# GL3520_4_Ports.net
KiCad netlist of a schematic drawn in Altium Designer
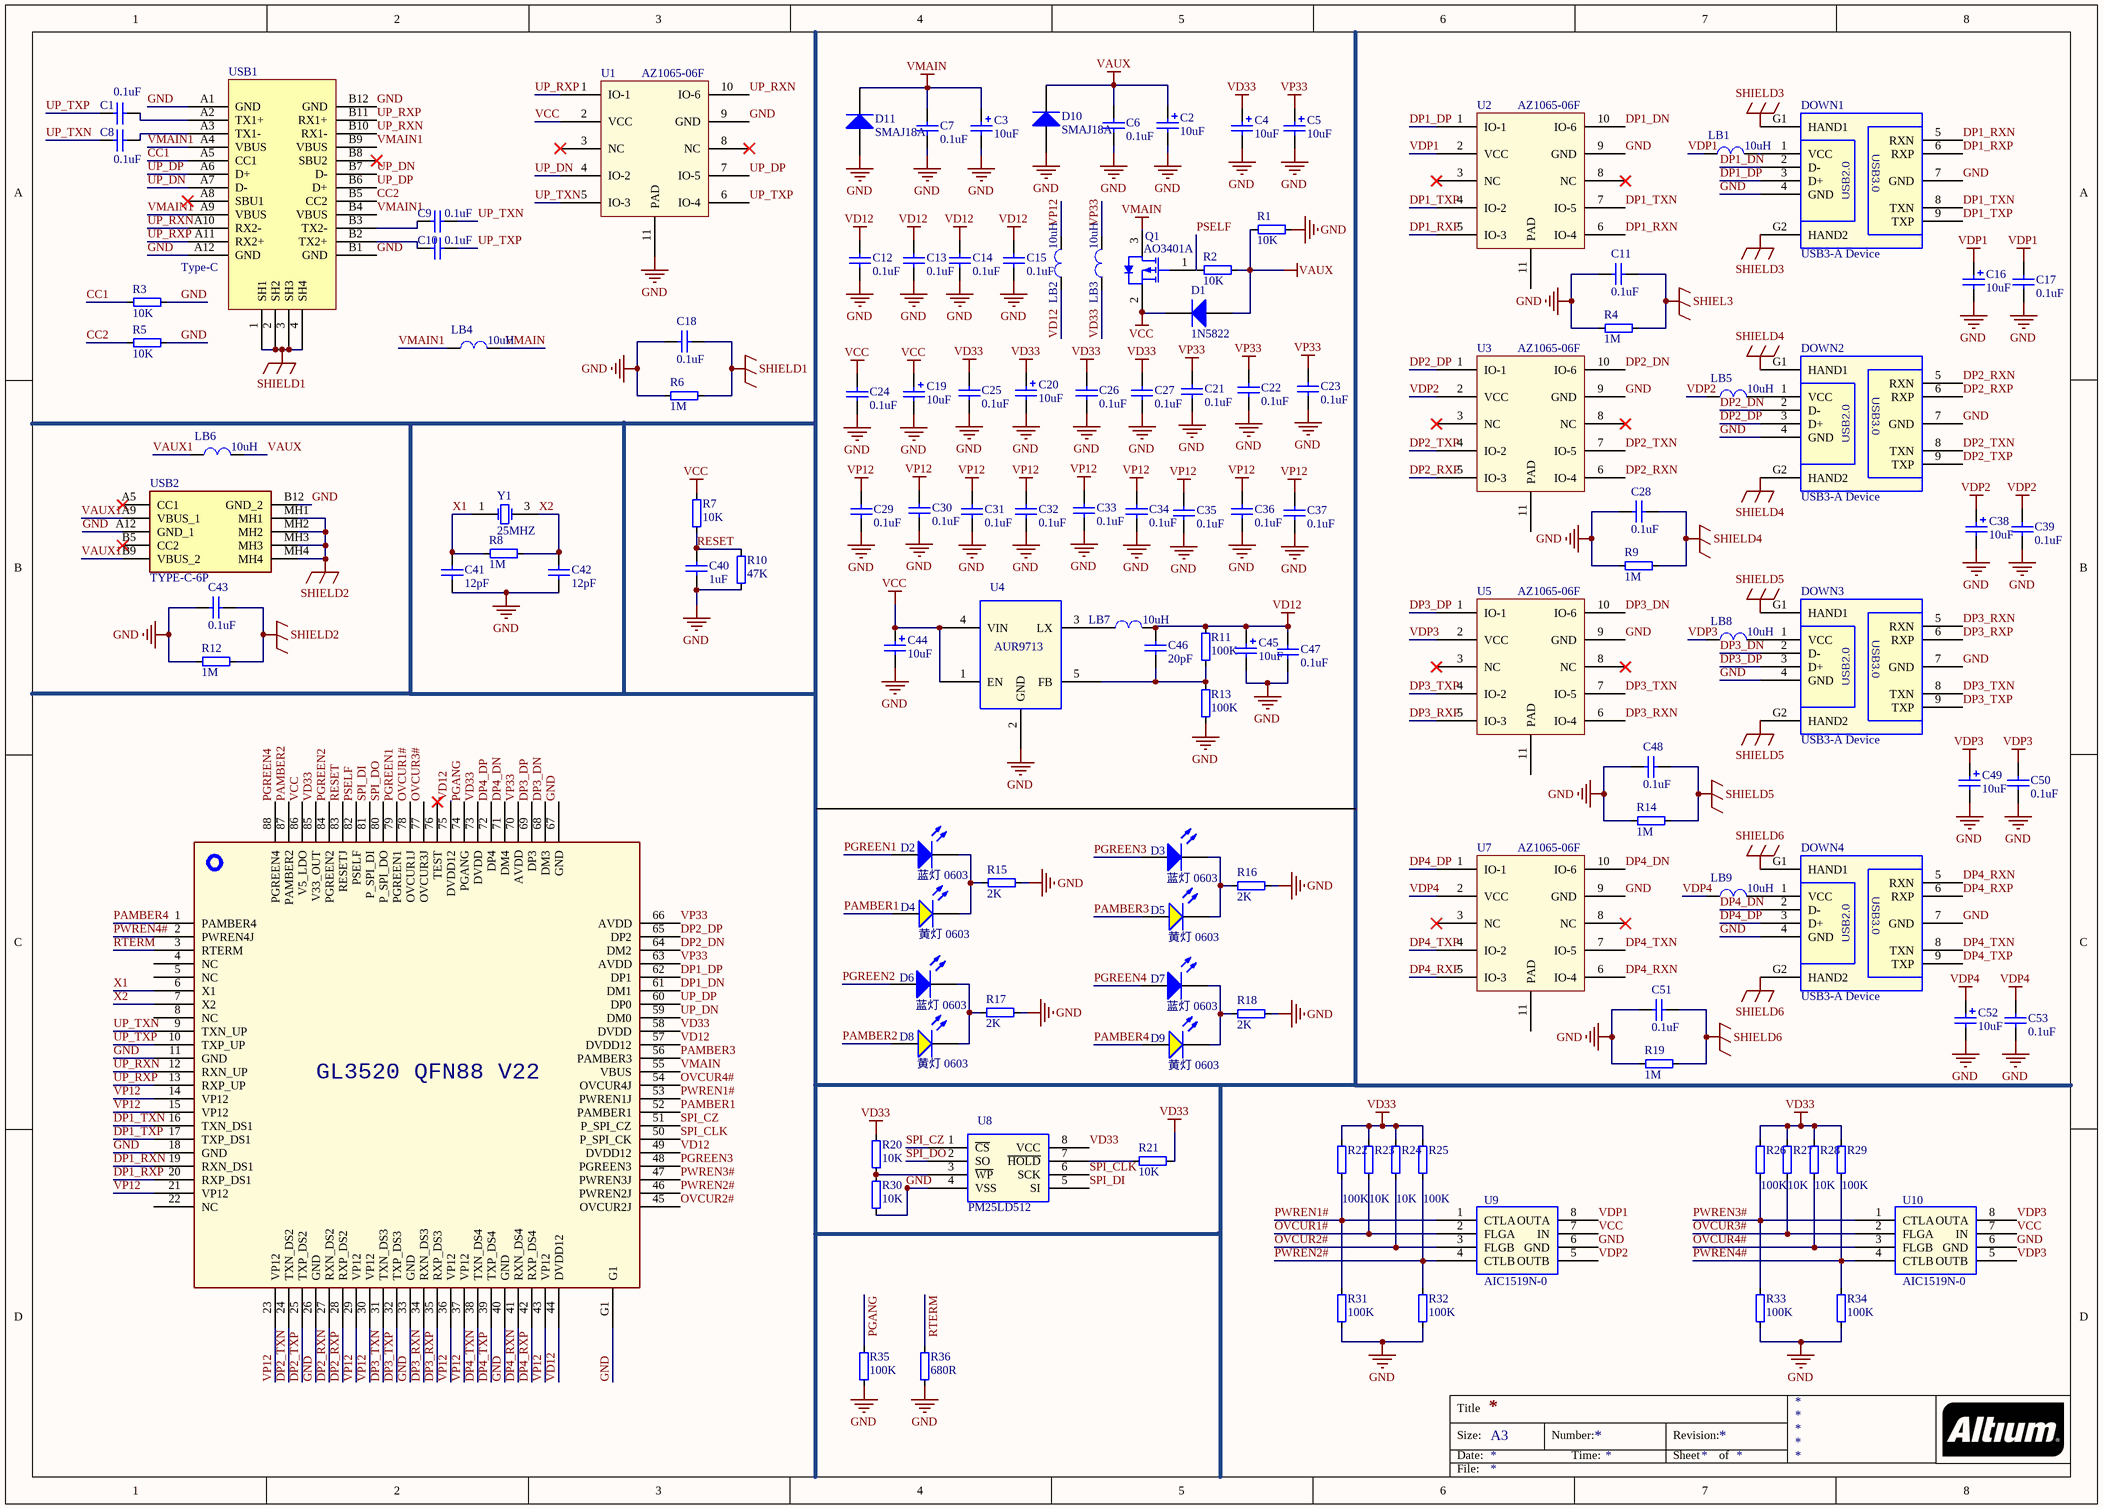
[diagram p0: GL3520 4 Ports.SchDoc]

(export (version "E")
  (design (tool "Eeschema 10.0.6"))
  (components
    (comp (ref "C1")
      (value "0.1uF")
      (footprint "C 0603_L")
      (description "贴片电容")
      (libsource (lib "嘉立创") (part "0603 2.2uF (225) 10% 16V"))
    )
    (comp (ref "C2")
      (value "10uF")
      (footprint "CASE-A_3216")
      (description "钽电容1206")
      (libsource (lib "嘉立创") (part "3216 10uF (106) 10% 16V"))
    )
    (comp (ref "C3")
      (value "10uF")
      (footprint "CASE-A_3216")
      (description "钽电容1206")
      (libsource (lib "嘉立创") (part "3216 10uF (106) 10% 16V"))
    )
    (comp (ref "C4")
      (value "10uF")
      (footprint "CASE-A_3216")
      (description "钽电容")
      (libsource (lib "嘉立创") (part "3216 10uF (106) 10% 16V"))
    )
    (comp (ref "C5")
      (value "10uF")
      (footprint "CASE-A_3216")
      (description "钽电容")
      (libsource (lib "嘉立创") (part "3216 10uF (106) 10% 16V"))
    )
    (comp (ref "C6")
      (value "0.1uF")
      (footprint "C 0603_L")
      (description "贴片电容")
      (libsource (lib "嘉立创") (part "0603 2.2uF (225) 10% 16V"))
    )
    (comp (ref "C7")
      (value "0.1uF")
      (footprint "C 0603_L")
      (description "贴片电容")
      (libsource (lib "嘉立创") (part "0603 2.2uF (225) 10% 16V"))
    )
    (comp (ref "C8")
      (value "0.1uF")
      (footprint "C 0603_L")
      (description "贴片电容")
      (libsource (lib "嘉立创") (part "0603 2.2uF (225) 10% 16V"))
    )
    (comp (ref "C9")
      (value "0.1uF")
      (footprint "C 0603_L")
      (description "贴片电容")
      (libsource (lib "嘉立创") (part "0603 2.2uF (225) 10% 16V"))
    )
    (comp (ref "C10")
      (value "0.1uF")
      (footprint "C 0603_L")
      (description "贴片电容")
      (libsource (lib "嘉立创") (part "0603 2.2uF (225) 10% 16V"))
    )
    (comp (ref "C11")
      (value "0.1uF")
      (footprint "C 0603_L")
      (description "贴片电容")
      (libsource (lib "嘉立创") (part "0603 2.2uF (225) 10% 16V"))
    )
    (comp (ref "C12")
      (value "0.1uF")
      (footprint "C 0603_L")
      (description "贴片电容")
      (libsource (lib "嘉立创") (part "0603 2.2uF (225) 10% 16V"))
    )
    (comp (ref "C13")
      (value "0.1uF")
      (footprint "C 0603_L")
      (description "贴片电容")
      (libsource (lib "嘉立创") (part "0603 2.2uF (225) 10% 16V"))
    )
    (comp (ref "C14")
      (value "0.1uF")
      (footprint "C 0603_L")
      (description "贴片电容")
      (libsource (lib "嘉立创") (part "0603 2.2uF (225) 10% 16V"))
    )
    (comp (ref "C15")
      (value "0.1uF")
      (footprint "C 0603_L")
      (description "贴片电容")
      (libsource (lib "嘉立创") (part "0603 2.2uF (225) 10% 16V"))
    )
    (comp (ref "C16")
      (value "10uF")
      (footprint "CASE-A_3216")
      (description "钽电容")
      (libsource (lib "嘉立创") (part "3216 10uF (106) 10% 16V"))
    )
    (comp (ref "C17")
      (value "0.1uF")
      (footprint "C 0603_L")
      (description "贴片电容")
      (libsource (lib "嘉立创") (part "0603 2.2uF (225) 10% 16V"))
    )
    (comp (ref "C18")
      (value "0.1uF")
      (footprint "C 0603_L")
      (description "贴片电容")
      (libsource (lib "嘉立创") (part "0603 2.2uF (225) 10% 16V"))
    )
    (comp (ref "C19")
      (value "10uF")
      (footprint "CASE-A_3216")
      (description "钽电容1206")
      (libsource (lib "嘉立创") (part "3216 10uF (106) 10% 16V"))
    )
    (comp (ref "C20")
      (value "10uF")
      (footprint "CASE-A_3216")
      (description "钽电容1206")
      (libsource (lib "嘉立创") (part "3216 10uF (106) 10% 16V"))
    )
    (comp (ref "C21")
      (value "0.1uF")
      (footprint "C 0603_L")
      (description "贴片电容")
      (libsource (lib "嘉立创") (part "0603 2.2uF (225) 10% 16V"))
    )
    (comp (ref "C22")
      (value "0.1uF")
      (footprint "C 0603_L")
      (description "贴片电容")
      (libsource (lib "嘉立创") (part "0603 2.2uF (225) 10% 16V"))
    )
    (comp (ref "C23")
      (value "0.1uF")
      (footprint "C 0603_L")
      (description "贴片电容")
      (libsource (lib "嘉立创") (part "0603 2.2uF (225) 10% 16V"))
    )
    (comp (ref "C24")
      (value "0.1uF")
      (footprint "C 0603_L")
      (description "贴片电容")
      (libsource (lib "嘉立创") (part "0603 2.2uF (225) 10% 16V"))
    )
    (comp (ref "C25")
      (value "0.1uF")
      (footprint "C 0603_L")
      (description "贴片电容")
      (libsource (lib "嘉立创") (part "0603 2.2uF (225) 10% 16V"))
    )
    (comp (ref "C26")
      (value "0.1uF")
      (footprint "C 0603_L")
      (description "贴片电容")
      (libsource (lib "嘉立创") (part "0603 2.2uF (225) 10% 16V"))
    )
    (comp (ref "C27")
      (value "0.1uF")
      (footprint "C 0603_L")
      (description "贴片电容")
      (libsource (lib "嘉立创") (part "0603 2.2uF (225) 10% 16V"))
    )
    (comp (ref "C28")
      (value "0.1uF")
      (footprint "C 0603_L")
      (description "贴片电容")
      (libsource (lib "嘉立创") (part "0603 2.2uF (225) 10% 16V"))
    )
    (comp (ref "C29")
      (value "0.1uF")
      (footprint "C 0603_L")
      (description "贴片电容")
      (libsource (lib "嘉立创") (part "0603 2.2uF (225) 10% 16V"))
    )
    (comp (ref "C30")
      (value "0.1uF")
      (footprint "C 0603_L")
      (description "贴片电容")
      (libsource (lib "嘉立创") (part "0603 2.2uF (225) 10% 16V"))
    )
    (comp (ref "C31")
      (value "0.1uF")
      (footprint "C 0603_L")
      (description "贴片电容")
      (libsource (lib "嘉立创") (part "0603 2.2uF (225) 10% 16V"))
    )
    (comp (ref "C32")
      (value "0.1uF")
      (footprint "C 0603_L")
      (description "贴片电容")
      (libsource (lib "嘉立创") (part "0603 2.2uF (225) 10% 16V"))
    )
    (comp (ref "C33")
      (value "0.1uF")
      (footprint "C 0603_L")
      (description "贴片电容")
      (libsource (lib "嘉立创") (part "0603 2.2uF (225) 10% 16V"))
    )
    (comp (ref "C34")
      (value "0.1uF")
      (footprint "C 0603_L")
      (description "贴片电容")
      (libsource (lib "嘉立创") (part "0603 2.2uF (225) 10% 16V"))
    )
    (comp (ref "C35")
      (value "0.1uF")
      (footprint "C 0603_L")
      (description "贴片电容")
      (libsource (lib "嘉立创") (part "0603 2.2uF (225) 10% 16V"))
    )
    (comp (ref "C36")
      (value "0.1uF")
      (footprint "C 0603_L")
      (description "贴片电容")
      (libsource (lib "嘉立创") (part "0603 2.2uF (225) 10% 16V"))
    )
    (comp (ref "C37")
      (value "0.1uF")
      (footprint "C 0603_L")
      (description "贴片电容")
      (libsource (lib "嘉立创") (part "0603 2.2uF (225) 10% 16V"))
    )
    (comp (ref "C38")
      (value "10uF")
      (footprint "CASE-A_3216")
      (description "钽电容")
      (libsource (lib "嘉立创") (part "3216 10uF (106) 10% 16V"))
    )
    (comp (ref "C39")
      (value "0.1uF")
      (footprint "C 0603_L")
      (description "贴片电容")
      (libsource (lib "嘉立创") (part "0603 2.2uF (225) 10% 16V"))
    )
    (comp (ref "C40")
      (value "1uF")
      (footprint "C 0603_L")
      (description "贴片电容")
      (libsource (lib "嘉立创") (part "0603 2.2uF (225) 10% 16V"))
    )
    (comp (ref "C41")
      (value "12pF")
      (footprint "C 0603_L")
      (description "贴片电容")
      (libsource (lib "嘉立创") (part "0603 2.2uF (225) 10% 16V"))
    )
    (comp (ref "C42")
      (value "12pF")
      (footprint "C 0603_L")
      (description "贴片电容")
      (libsource (lib "嘉立创") (part "0603 2.2uF (225) 10% 16V"))
    )
    (comp (ref "C43")
      (value "0.1uF")
      (footprint "C 0603_L")
      (description "贴片电容")
      (libsource (lib "嘉立创") (part "0603 2.2uF (225) 10% 16V"))
    )
    (comp (ref "C44")
      (value "10uF")
      (footprint "CASE-A_3216")
      (description "钽电容")
      (libsource (lib "嘉立创") (part "3216 10uF (106) 10% 16V"))
    )
    (comp (ref "C45")
      (value "10uF")
      (footprint "CASE-A_3216")
      (description "钽电容")
      (libsource (lib "嘉立创") (part "3216 10uF (106) 10% 16V"))
    )
    (comp (ref "C46")
      (value "20pF")
      (footprint "C 0603_L")
      (description "贴片电容")
      (libsource (lib "嘉立创") (part "0603 2.2uF (225) 10% 16V"))
    )
    (comp (ref "C47")
      (value "0.1uF")
      (footprint "C 0603_L")
      (description "贴片电容")
      (libsource (lib "嘉立创") (part "0603 2.2uF (225) 10% 16V"))
    )
    (comp (ref "C48")
      (value "0.1uF")
      (footprint "C 0603_L")
      (description "贴片电容")
      (libsource (lib "嘉立创") (part "0603 2.2uF (225) 10% 16V"))
    )
    (comp (ref "C49")
      (value "10uF")
      (footprint "CASE-A_3216")
      (description "钽电容")
      (libsource (lib "嘉立创") (part "3216 10uF (106) 10% 16V"))
    )
    (comp (ref "C50")
      (value "0.1uF")
      (footprint "C 0603_L")
      (description "贴片电容")
      (libsource (lib "嘉立创") (part "0603 2.2uF (225) 10% 16V"))
    )
    (comp (ref "C51")
      (value "0.1uF")
      (footprint "C 0603_L")
      (description "贴片电容")
      (libsource (lib "嘉立创") (part "0603 2.2uF (225) 10% 16V"))
    )
    (comp (ref "C52")
      (value "10uF")
      (footprint "CASE-A_3216")
      (description "钽电容")
      (libsource (lib "嘉立创") (part "3216 10uF (106) 10% 16V"))
    )
    (comp (ref "C53")
      (value "0.1uF")
      (footprint "C 0603_L")
      (description "贴片电容")
      (libsource (lib "嘉立创") (part "0603 2.2uF (225) 10% 16V"))
    )
    (comp (ref "D1")
      (value "1N5822")
      (footprint "SMA")
      (description "3 Amp General Purpose Rectifier")
      (fields (field (name "PUBLISHER") "Altium Limited"))
      (libsource (lib "Miscellaneous Devices") (part "Diode 1N5400"))
    )
    (comp (ref "D2")
      (value "蓝灯 0603")
      (footprint "0603_LED_S1")
      (description "发光二极管")
      (libsource (lib "嘉立创") (part "0603 蓝灯"))
    )
    (comp (ref "D3")
      (value "蓝灯 0603")
      (footprint "0603_LED_S1")
      (description "发光二极管")
      (libsource (lib "嘉立创") (part "0603 蓝灯"))
    )
    (comp (ref "D4")
      (value "黄灯 0603")
      (footprint "0603_LED_S1")
      (description "发光二极管")
      (libsource (lib "嘉立创") (part "0603 黄灯"))
    )
    (comp (ref "D5")
      (value "黄灯 0603")
      (footprint "0603_LED_S1")
      (description "发光二极管")
      (libsource (lib "嘉立创") (part "0603 黄灯"))
    )
    (comp (ref "D6")
      (value "蓝灯 0603")
      (footprint "0603_LED_S1")
      (description "发光二极管")
      (libsource (lib "嘉立创") (part "0603 蓝灯"))
    )
    (comp (ref "D7")
      (value "蓝灯 0603")
      (footprint "0603_LED_S1")
      (description "发光二极管")
      (libsource (lib "嘉立创") (part "0603 蓝灯"))
    )
    (comp (ref "D8")
      (value "黄灯 0603")
      (footprint "0603_LED_S1")
      (description "发光二极管")
      (libsource (lib "嘉立创") (part "0603 黄灯"))
    )
    (comp (ref "D9")
      (value "黄灯 0603")
      (footprint "0603_LED_S1")
      (description "发光二极管")
      (libsource (lib "嘉立创") (part "0603 黄灯"))
    )
    (comp (ref "D10")
      (value "SMAJ18A")
      (footprint "DIO-214AC")
      (description "3 Amp General Purpose Rectifier")
      (fields (field (name "PUBLISHER") "Altium Limited"))
      (libsource (lib "Miscellaneous Devices") (part "Diode 1N5400"))
    )
    (comp (ref "D11")
      (value "SMAJ18A")
      (footprint "DIO-214AC")
      (description "3 Amp General Purpose Rectifier")
      (fields (field (name "PUBLISHER") "Altium Limited"))
      (libsource (lib "Miscellaneous Devices") (part "Diode 1N5400"))
    )
    (comp (ref "DOWN1")
      (value "USB3-A Device")
      (footprint "USB3.0-2 - duplicate")
      (libsource (lib "*") (part "USB3-A_5"))
    )
    (comp (ref "DOWN2")
      (value "USB3-A Device")
      (footprint "USB3.0-2 - duplicate")
      (libsource (lib "*") (part "USB3-A_5"))
    )
    (comp (ref "DOWN3")
      (value "USB3-A Device")
      (footprint "USB3.0-2 - duplicate")
      (libsource (lib "*") (part "USB3-A_5"))
    )
    (comp (ref "DOWN4")
      (value "USB3-A Device")
      (footprint "USB3.0-2 - duplicate")
      (libsource (lib "*") (part "USB3-A_5"))
    )
    (comp (ref "LB1") (value "10uH") (footprint "CDRH74") (libsource (lib "*") (part "L-0603")))
    (comp (ref "LB2") (value "10uH") (footprint "CDRH74") (libsource (lib "*") (part "L-0603")))
    (comp (ref "LB3") (value "10uH") (footprint "CDRH74") (libsource (lib "*") (part "L-0603")))
    (comp (ref "LB4") (value "10uH") (footprint "CDRH74") (libsource (lib "*") (part "L-0603")))
    (comp (ref "LB5") (value "10uH") (footprint "CDRH74") (libsource (lib "*") (part "L-0603")))
    (comp (ref "LB6") (value "10uH") (footprint "CDRH74") (libsource (lib "*") (part "L-0603")))
    (comp (ref "LB7") (value "10uH") (footprint "CDRH74") (libsource (lib "*") (part "L-0603")))
    (comp (ref "LB8") (value "10uH") (footprint "CDRH74") (libsource (lib "*") (part "L-0603")))
    (comp (ref "LB9") (value "10uH") (footprint "CDRH74") (libsource (lib "*") (part "L-0603")))
    (comp (ref "Q1")
      (value "AO3401A")
      (footprint "SOT23-3L")
      (description "P-Channel MOSFET, 30 V, 4 A, -55 to 150 degC, 3-Pin SOT-23-3L, RoHS, Tape and Reel")
      (fields (field (name "MANUFACTURER") "Alpha and Omega"))
      (libsource (lib "GL3520 4 Ports") (part "CMP-2000-05778-1"))
    )
    (comp (ref "R1") (value "10K") (footprint "R 0603_L") (libsource (lib "Jlink OB") (part "RES")))
    (comp (ref "R2") (value "10K") (footprint "R 0603_L") (libsource (lib "Jlink OB") (part "RES")))
    (comp (ref "R3") (value "10K") (footprint "R 0603_L") (libsource (lib "Jlink OB") (part "RES")))
    (comp (ref "R4") (value "1M") (footprint "R 0603_L") (libsource (lib "Jlink OB") (part "RES")))
    (comp (ref "R5") (value "10K") (footprint "R 0603_L") (libsource (lib "Jlink OB") (part "RES")))
    (comp (ref "R6") (value "1M") (footprint "R 0603_L") (libsource (lib "Jlink OB") (part "RES")))
    (comp (ref "R7") (value "10K") (footprint "R 0603_L") (libsource (lib "Jlink OB") (part "RES")))
    (comp (ref "R8") (value "1M") (footprint "R 0603_L") (libsource (lib "Jlink OB") (part "RES")))
    (comp (ref "R9") (value "1M") (footprint "R 0603_L") (libsource (lib "Jlink OB") (part "RES")))
    (comp (ref "R10") (value "47K") (footprint "R 0603_L") (libsource (lib "Jlink OB") (part "RES")))
    (comp (ref "R11") (value "100K") (footprint "R 0603_L") (libsource (lib "Jlink OB") (part "RES")))
    (comp (ref "R12") (value "1M") (footprint "R 0603_L") (libsource (lib "Jlink OB") (part "RES")))
    (comp (ref "R13") (value "100K") (footprint "R 0603_L") (libsource (lib "Jlink OB") (part "RES")))
    (comp (ref "R14") (value "1M") (footprint "R 0603_L") (libsource (lib "Jlink OB") (part "RES")))
    (comp (ref "R15") (value "2K") (footprint "R 0603_L") (libsource (lib "Jlink OB") (part "RES")))
    (comp (ref "R16") (value "2K") (footprint "R 0603_L") (libsource (lib "Jlink OB") (part "RES")))
    (comp (ref "R17") (value "2K") (footprint "R 0603_L") (libsource (lib "Jlink OB") (part "RES")))
    (comp (ref "R18") (value "2K") (footprint "R 0603_L") (libsource (lib "Jlink OB") (part "RES")))
    (comp (ref "R19") (value "1M") (footprint "R 0603_L") (libsource (lib "Jlink OB") (part "RES")))
    (comp (ref "R20") (value "10K") (footprint "R 0603_L") (libsource (lib "Jlink OB") (part "RES")))
    (comp (ref "R21") (value "10K") (footprint "R 0603_L") (libsource (lib "Jlink OB") (part "RES")))
    (comp (ref "R22") (value "100K") (footprint "R 0603_L") (libsource (lib "Jlink OB") (part "RES")))
    (comp (ref "R23") (value "10K") (footprint "R 0603_L") (libsource (lib "Jlink OB") (part "RES")))
    (comp (ref "R24") (value "10K") (footprint "R 0603_L") (libsource (lib "Jlink OB") (part "RES")))
    (comp (ref "R25") (value "100K") (footprint "R 0603_L") (libsource (lib "Jlink OB") (part "RES")))
    (comp (ref "R26") (value "100K") (footprint "R 0603_L") (libsource (lib "Jlink OB") (part "RES")))
    (comp (ref "R27") (value "10K") (footprint "R 0603_L") (libsource (lib "Jlink OB") (part "RES")))
    (comp (ref "R28") (value "10K") (footprint "R 0603_L") (libsource (lib "Jlink OB") (part "RES")))
    (comp (ref "R29") (value "100K") (footprint "R 0603_L") (libsource (lib "Jlink OB") (part "RES")))
    (comp (ref "R30") (value "10K") (footprint "R 0603_L") (libsource (lib "Jlink OB") (part "RES")))
    (comp (ref "R31") (value "100K") (footprint "R 0603_L") (libsource (lib "Jlink OB") (part "RES")))
    (comp (ref "R32") (value "100K") (footprint "R 0603_L") (libsource (lib "Jlink OB") (part "RES")))
    (comp (ref "R33") (value "100K") (footprint "R 0603_L") (libsource (lib "Jlink OB") (part "RES")))
    (comp (ref "R34") (value "100K") (footprint "R 0603_L") (libsource (lib "Jlink OB") (part "RES")))
    (comp (ref "R35") (value "100K") (footprint "R 0603_L") (libsource (lib "Jlink OB") (part "RES")))
    (comp (ref "R36") (value "680R") (footprint "R 0603_L") (libsource (lib "Jlink OB") (part "RES")))
    (comp (ref "U1")
      (value "AZ1065-06F")
      (footprint "DFN4120P10E")
      (description "晶炎AZ1065-06F.R7G DFN4120 丝印119 ESD/TVS静电保护二极管")
      (libsource (lib "GL3520 4 Ports") (part "AZ1065-06F"))
    )
    (comp (ref "U2")
      (value "AZ1065-06F")
      (footprint "DFN4120P10E")
      (description "晶炎AZ1065-06F.R7G DFN4120 丝印119 ESD/TVS静电保护二极管")
      (libsource (lib "GL3520 4 Ports") (part "AZ1065-06F"))
    )
    (comp (ref "U3")
      (value "AZ1065-06F")
      (footprint "DFN4120P10E")
      (description "晶炎AZ1065-06F.R7G DFN4120 丝印119 ESD/TVS静电保护二极管")
      (libsource (lib "GL3520 4 Ports") (part "AZ1065-06F"))
    )
    (comp (ref "U4") (value "AUR9713") (footprint "SOT23-5L") (libsource (lib "*") (part "AUR9705_3")))
    (comp (ref "U5")
      (value "AZ1065-06F")
      (footprint "DFN4120P10E")
      (description "晶炎AZ1065-06F.R7G DFN4120 丝印119 ESD/TVS静电保护二极管")
      (libsource (lib "GL3520 4 Ports") (part "AZ1065-06F"))
    )
    (comp (ref "U6")
      (value "GL3520_QFN88_V094-1_22")
      (footprint "QFN88")
      (libsource (lib "GL3520 4 Ports") (part "GL3520_QFN88_V094-1_22"))
    )
    (comp (ref "U7")
      (value "AZ1065-06F")
      (footprint "DFN4120P10E")
      (description "晶炎AZ1065-06F.R7G DFN4120 丝印119 ESD/TVS静电保护二极管")
      (libsource (lib "GL3520 4 Ports") (part "AZ1065-06F"))
    )
    (comp (ref "U8") (value "PM25LD512") (footprint "SOP8W_M") (libsource (lib "*") (part "CAT25C128/256")))
    (comp (ref "U9") (value "AIC1519N-0") (footprint "SOP8_L") (libsource (lib "*") (part "AIC1526-SOP")))
    (comp (ref "U10") (value "AIC1519N-0") (footprint "SOP8_L") (libsource (lib "*") (part "AIC1526-SOP")))
    (comp (ref "USB1")
      (value "Type-C")
      (footprint "USB_TYPE_C_24P - duplicate")
      (libsource (lib "Jlink OB") (part "Type-C"))
    )
    (comp (ref "USB2")
      (value "TYPE-C-6P")
      (footprint "USB_TYPE_C_6P")
      (description "Connector")
      (fields (field (name "MANUFACTURER_PART_NUMBER") "TYPE-C-31-M-17"))
      (libsource (lib "SamacSys") (part "TYPE-C-31-M-17"))
    )
    (comp (ref "Y1")
      (value "25MHZ")
      (footprint "OSC 3225-4P")
      (description "贴片晶振")
      (libsource (lib "嘉立创") (part "SMD-3225_4P  25MHZ 12PF 10PPM"))
    )
  )
  (nets
    (net (code "1") (name "/CC1") (class "Default")
      (node (ref "R3") (pin "1") (pinfunction "1_1") (pintype "passive"))
      (node (ref "USB1") (pin "A5") (pinfunction "CC1_A5") (pintype "passive"))
    )
    (net (code "2") (name "/CC2") (class "Default")
      (node (ref "R5") (pin "1") (pinfunction "1_1") (pintype "passive"))
      (node (ref "USB1") (pin "B5") (pinfunction "CC2_B5") (pintype "passive"))
    )
    (net (code "3") (name "/DP1_DN") (class "Default")
      (node (ref "DOWN1") (pin "2") (pinfunction "D-_2") (pintype "passive"))
      (node (ref "U2") (pin "10") (pinfunction "IO-6_10") (pintype "passive"))
      (node (ref "U6") (pin "61") (pinfunction "DM1_61") (pintype "passive"))
    )
    (net (code "4") (name "/DP1_DP") (class "Default")
      (node (ref "DOWN1") (pin "3") (pinfunction "D+_3") (pintype "passive"))
      (node (ref "U2") (pin "1") (pinfunction "IO-1_1") (pintype "passive"))
      (node (ref "U6") (pin "62") (pinfunction "DP1_62") (pintype "passive"))
    )
    (net (code "5") (name "/DP1_RXN") (class "Default")
      (node (ref "DOWN1") (pin "5") (pinfunction "RXN_5") (pintype "passive"))
      (node (ref "U2") (pin "6") (pinfunction "IO-4_6") (pintype "passive"))
      (node (ref "U6") (pin "19") (pinfunction "RXN_DS1_19") (pintype "passive"))
    )
    (net (code "6") (name "/DP1_RXP") (class "Default")
      (node (ref "DOWN1") (pin "6") (pinfunction "RXP_6") (pintype "passive"))
      (node (ref "U2") (pin "5") (pinfunction "IO-3_5") (pintype "passive"))
      (node (ref "U6") (pin "20") (pinfunction "RXP_DS1_20") (pintype "passive"))
    )
    (net (code "7") (name "/DP1_TXN") (class "Default")
      (node (ref "DOWN1") (pin "8") (pinfunction "TXN_8") (pintype "passive"))
      (node (ref "U2") (pin "7") (pinfunction "IO-5_7") (pintype "passive"))
      (node (ref "U6") (pin "16") (pinfunction "TXN_DS1_16") (pintype "passive"))
    )
    (net (code "8") (name "/DP1_TXP") (class "Default")
      (node (ref "DOWN1") (pin "9") (pinfunction "TXP_9") (pintype "passive"))
      (node (ref "U2") (pin "4") (pinfunction "IO-2_4") (pintype "passive"))
      (node (ref "U6") (pin "17") (pinfunction "TXP_DS1_17") (pintype "passive"))
    )
    (net (code "9") (name "/DP2_DN") (class "Default")
      (node (ref "DOWN2") (pin "2") (pinfunction "D-_2") (pintype "passive"))
      (node (ref "U3") (pin "10") (pinfunction "IO-6_10") (pintype "passive"))
      (node (ref "U6") (pin "64") (pinfunction "DM2_64") (pintype "passive"))
    )
    (net (code "10") (name "/DP2_DP") (class "Default")
      (node (ref "DOWN2") (pin "3") (pinfunction "D+_3") (pintype "passive"))
      (node (ref "U3") (pin "1") (pinfunction "IO-1_1") (pintype "passive"))
      (node (ref "U6") (pin "65") (pinfunction "DP2_65") (pintype "passive"))
    )
    (net (code "11") (name "/DP2_RXN") (class "Default")
      (node (ref "DOWN2") (pin "5") (pinfunction "RXN_5") (pintype "passive"))
      (node (ref "U3") (pin "6") (pinfunction "IO-4_6") (pintype "passive"))
      (node (ref "U6") (pin "27") (pinfunction "RXN_DS2_27") (pintype "passive"))
    )
    (net (code "12") (name "/DP2_RXP") (class "Default")
      (node (ref "DOWN2") (pin "6") (pinfunction "RXP_6") (pintype "passive"))
      (node (ref "U3") (pin "5") (pinfunction "IO-3_5") (pintype "passive"))
      (node (ref "U6") (pin "28") (pinfunction "RXP_DS2_28") (pintype "passive"))
    )
    (net (code "13") (name "/DP2_TXN") (class "Default")
      (node (ref "DOWN2") (pin "8") (pinfunction "TXN_8") (pintype "passive"))
      (node (ref "U3") (pin "7") (pinfunction "IO-5_7") (pintype "passive"))
      (node (ref "U6") (pin "24") (pinfunction "TXN_DS2_24") (pintype "passive"))
    )
    (net (code "14") (name "/DP2_TXP") (class "Default")
      (node (ref "DOWN2") (pin "9") (pinfunction "TXP_9") (pintype "passive"))
      (node (ref "U3") (pin "4") (pinfunction "IO-2_4") (pintype "passive"))
      (node (ref "U6") (pin "25") (pinfunction "TXP_DS2_25") (pintype "passive"))
    )
    (net (code "15") (name "/DP3_DN") (class "Default")
      (node (ref "DOWN3") (pin "2") (pinfunction "D-_2") (pintype "passive"))
      (node (ref "U5") (pin "10") (pinfunction "IO-6_10") (pintype "passive"))
      (node (ref "U6") (pin "68") (pinfunction "DM3_68") (pintype "passive"))
    )
    (net (code "16") (name "/DP3_DP") (class "Default")
      (node (ref "DOWN3") (pin "3") (pinfunction "D+_3") (pintype "passive"))
      (node (ref "U5") (pin "1") (pinfunction "IO-1_1") (pintype "passive"))
      (node (ref "U6") (pin "69") (pinfunction "DP3_69") (pintype "passive"))
    )
    (net (code "17") (name "/DP3_RXN") (class "Default")
      (node (ref "DOWN3") (pin "5") (pinfunction "RXN_5") (pintype "passive"))
      (node (ref "U5") (pin "6") (pinfunction "IO-4_6") (pintype "passive"))
      (node (ref "U6") (pin "34") (pinfunction "RXN_DS3_34") (pintype "passive"))
    )
    (net (code "18") (name "/DP3_RXP") (class "Default")
      (node (ref "DOWN3") (pin "6") (pinfunction "RXP_6") (pintype "passive"))
      (node (ref "U5") (pin "5") (pinfunction "IO-3_5") (pintype "passive"))
      (node (ref "U6") (pin "35") (pinfunction "RXP_DS3_35") (pintype "passive"))
    )
    (net (code "19") (name "/DP3_TXN") (class "Default")
      (node (ref "DOWN3") (pin "8") (pinfunction "TXN_8") (pintype "passive"))
      (node (ref "U5") (pin "7") (pinfunction "IO-5_7") (pintype "passive"))
      (node (ref "U6") (pin "31") (pinfunction "TXN_DS3_31") (pintype "passive"))
    )
    (net (code "20") (name "/DP3_TXP") (class "Default")
      (node (ref "DOWN3") (pin "9") (pinfunction "TXP_9") (pintype "passive"))
      (node (ref "U5") (pin "4") (pinfunction "IO-2_4") (pintype "passive"))
      (node (ref "U6") (pin "32") (pinfunction "TXP_DS3_32") (pintype "passive"))
    )
    (net (code "21") (name "/DP4_DN") (class "Default")
      (node (ref "DOWN4") (pin "2") (pinfunction "D-_2") (pintype "passive"))
      (node (ref "U6") (pin "71") (pinfunction "DM4_71") (pintype "passive"))
      (node (ref "U7") (pin "10") (pinfunction "IO-6_10") (pintype "passive"))
    )
    (net (code "22") (name "/DP4_DP") (class "Default")
      (node (ref "DOWN4") (pin "3") (pinfunction "D+_3") (pintype "passive"))
      (node (ref "U6") (pin "72") (pinfunction "DP4_72") (pintype "passive"))
      (node (ref "U7") (pin "1") (pinfunction "IO-1_1") (pintype "passive"))
    )
    (net (code "23") (name "/DP4_RXN") (class "Default")
      (node (ref "DOWN4") (pin "5") (pinfunction "RXN_5") (pintype "passive"))
      (node (ref "U6") (pin "41") (pinfunction "RXN_DS4_41") (pintype "passive"))
      (node (ref "U7") (pin "6") (pinfunction "IO-4_6") (pintype "passive"))
    )
    (net (code "24") (name "/DP4_RXP") (class "Default")
      (node (ref "DOWN4") (pin "6") (pinfunction "RXP_6") (pintype "passive"))
      (node (ref "U6") (pin "42") (pinfunction "RXP_DS4_42") (pintype "passive"))
      (node (ref "U7") (pin "5") (pinfunction "IO-3_5") (pintype "passive"))
    )
    (net (code "25") (name "/DP4_TXN") (class "Default")
      (node (ref "DOWN4") (pin "8") (pinfunction "TXN_8") (pintype "passive"))
      (node (ref "U6") (pin "38") (pinfunction "TXN_DS4_38") (pintype "passive"))
      (node (ref "U7") (pin "7") (pinfunction "IO-5_7") (pintype "passive"))
    )
    (net (code "26") (name "/DP4_TXP") (class "Default")
      (node (ref "DOWN4") (pin "9") (pinfunction "TXP_9") (pintype "passive"))
      (node (ref "U6") (pin "39") (pinfunction "TXP_DS4_39") (pintype "passive"))
      (node (ref "U7") (pin "4") (pinfunction "IO-2_4") (pintype "passive"))
    )
    (net (code "27") (name "/OVCUR1#") (class "Default")
      (node (ref "R23") (pin "2") (pinfunction "2_2") (pintype "passive"))
      (node (ref "U6") (pin "78") (pinfunction "OVCUR1J_78") (pintype "passive"))
      (node (ref "U9") (pin "2") (pinfunction "FLGA_2") (pintype "passive"))
    )
    (net (code "28") (name "/OVCUR2#") (class "Default")
      (node (ref "R24") (pin "2") (pinfunction "2_2") (pintype "passive"))
      (node (ref "U6") (pin "45") (pinfunction "OVCUR2J_45") (pintype "passive"))
      (node (ref "U9") (pin "3") (pinfunction "FLGB_3") (pintype "passive"))
    )
    (net (code "29") (name "/OVCUR3#") (class "Default")
      (node (ref "R27") (pin "2") (pinfunction "2_2") (pintype "passive"))
      (node (ref "U10") (pin "2") (pinfunction "FLGA_2") (pintype "passive"))
      (node (ref "U6") (pin "77") (pinfunction "OVCUR3J_77") (pintype "passive"))
    )
    (net (code "30") (name "/OVCUR4#") (class "Default")
      (node (ref "R28") (pin "2") (pinfunction "2_2") (pintype "passive"))
      (node (ref "U10") (pin "3") (pinfunction "FLGB_3") (pintype "passive"))
      (node (ref "U6") (pin "54") (pinfunction "OVCUR4J_54") (pintype "passive"))
    )
    (net (code "31") (name "/PAMBER1") (class "Default")
      (node (ref "D4") (pin "A") (pinfunction "A_A") (pintype "passive"))
      (node (ref "U6") (pin "52") (pinfunction "PAMBER1_52") (pintype "passive"))
    )
    (net (code "32") (name "/PAMBER2") (class "Default")
      (node (ref "D8") (pin "A") (pinfunction "A_A") (pintype "passive"))
      (node (ref "U6") (pin "87") (pinfunction "PAMBER2_87") (pintype "passive"))
    )
    (net (code "33") (name "/PAMBER3") (class "Default")
      (node (ref "D5") (pin "A") (pinfunction "A_A") (pintype "passive"))
      (node (ref "U6") (pin "56") (pinfunction "PAMBER3_56") (pintype "passive"))
    )
    (net (code "34") (name "/PAMBER4") (class "Default")
      (node (ref "D9") (pin "A") (pinfunction "A_A") (pintype "passive"))
      (node (ref "U6") (pin "1") (pinfunction "PAMBER4_1") (pintype "passive"))
    )
    (net (code "35") (name "/PGANG") (class "Default")
      (node (ref "R35") (pin "1") (pinfunction "1_1") (pintype "passive"))
      (node (ref "U6") (pin "74") (pinfunction "PGANG_74") (pintype "passive"))
    )
    (net (code "36") (name "/PGREEN1") (class "Default")
      (node (ref "D2") (pin "A") (pinfunction "A_A") (pintype "passive"))
      (node (ref "U6") (pin "79") (pinfunction "PGREEN1_79") (pintype "passive"))
    )
    (net (code "37") (name "/PGREEN2") (class "Default")
      (node (ref "D6") (pin "A") (pinfunction "A_A") (pintype "passive"))
      (node (ref "U6") (pin "84") (pinfunction "PGREEN2_84") (pintype "passive"))
    )
    (net (code "38") (name "/PGREEN3") (class "Default")
      (node (ref "D3") (pin "A") (pinfunction "A_A") (pintype "passive"))
      (node (ref "U6") (pin "48") (pinfunction "PGREEN3_48") (pintype "passive"))
    )
    (net (code "39") (name "/PGREEN4") (class "Default")
      (node (ref "D7") (pin "A") (pinfunction "A_A") (pintype "passive"))
      (node (ref "U6") (pin "88") (pinfunction "PGREEN4_88") (pintype "passive"))
    )
    (net (code "40") (name "/PSELF") (class "Default")
      (node (ref "Q1") (pin "1") (pinfunction "GATE_1") (pintype "passive"))
      (node (ref "U6") (pin "82") (pinfunction "PSELF_82") (pintype "passive"))
    )
    (net (code "41") (name "/PWREN1#") (class "Default")
      (node (ref "R22") (pin "2") (pinfunction "2_2") (pintype "passive"))
      (node (ref "R31") (pin "1") (pinfunction "1_1") (pintype "passive"))
      (node (ref "U6") (pin "53") (pinfunction "PWREN1J_53") (pintype "passive"))
      (node (ref "U9") (pin "1") (pinfunction "CTLA_1") (pintype "passive"))
    )
    (net (code "42") (name "/PWREN2#") (class "Default")
      (node (ref "R25") (pin "2") (pinfunction "2_2") (pintype "passive"))
      (node (ref "R32") (pin "1") (pinfunction "1_1") (pintype "passive"))
      (node (ref "U6") (pin "46") (pinfunction "PWREN2J_46") (pintype "passive"))
      (node (ref "U9") (pin "4") (pinfunction "CTLB_4") (pintype "passive"))
    )
    (net (code "43") (name "/PWREN3#") (class "Default")
      (node (ref "R26") (pin "2") (pinfunction "2_2") (pintype "passive"))
      (node (ref "R33") (pin "1") (pinfunction "1_1") (pintype "passive"))
      (node (ref "U10") (pin "1") (pinfunction "CTLA_1") (pintype "passive"))
      (node (ref "U6") (pin "47") (pinfunction "PWREN3J_47") (pintype "passive"))
    )
    (net (code "44") (name "/PWREN4#") (class "Default")
      (node (ref "R29") (pin "2") (pinfunction "2_2") (pintype "passive"))
      (node (ref "R34") (pin "1") (pinfunction "1_1") (pintype "passive"))
      (node (ref "U10") (pin "4") (pinfunction "CTLB_4") (pintype "passive"))
      (node (ref "U6") (pin "2") (pinfunction "PWREN4J_2") (pintype "passive"))
    )
    (net (code "45") (name "/RESET") (class "Default")
      (node (ref "C40") (pin "2") (pinfunction "2_2") (pintype "passive"))
      (node (ref "R10") (pin "2") (pinfunction "2_2") (pintype "passive"))
      (node (ref "R7") (pin "1") (pinfunction "1_1") (pintype "passive"))
      (node (ref "U6") (pin "83") (pinfunction "RESETJ_83") (pintype "passive"))
    )
    (net (code "46") (name "/RTERM") (class "Default")
      (node (ref "R36") (pin "1") (pinfunction "1_1") (pintype "passive"))
      (node (ref "U6") (pin "3") (pinfunction "RTERM_3") (pintype "passive"))
    )
    (net (code "47") (name "/SPI_CLK") (class "Default")
      (node (ref "U6") (pin "50") (pinfunction "P_SPI_CK_50") (pintype "passive"))
      (node (ref "U8") (pin "6") (pinfunction "SCK_6") (pintype "passive"))
    )
    (net (code "48") (name "/SPI_CZ") (class "Default")
      (node (ref "U6") (pin "51") (pinfunction "P_SPI_CZ_51") (pintype "passive"))
      (node (ref "U8") (pin "1") (pinfunction "~{CS}_1") (pintype "passive"))
    )
    (net (code "49") (name "/SPI_DI") (class "Default")
      (node (ref "U6") (pin "81") (pinfunction "P_SPI_DI_81") (pintype "passive"))
      (node (ref "U8") (pin "5") (pinfunction "SI_5") (pintype "passive"))
    )
    (net (code "50") (name "/SPI_DO") (class "Default")
      (node (ref "U6") (pin "80") (pinfunction "P_SPI_DO_80") (pintype "passive"))
      (node (ref "U8") (pin "2") (pinfunction "SO_2") (pintype "passive"))
    )
    (net (code "51") (name "/UP_DN") (class "Default")
      (node (ref "U1") (pin "4") (pinfunction "IO-2_4") (pintype "passive"))
      (node (ref "U6") (pin "59") (pinfunction "DM0_59") (pintype "passive"))
      (node (ref "USB1") (pin "A7") (pinfunction "D-_A7") (pintype "passive"))
      (node (ref "USB1") (pin "B7") (pinfunction "D-_B7") (pintype "passive"))
    )
    (net (code "52") (name "/UP_DP") (class "Default")
      (node (ref "U1") (pin "7") (pinfunction "IO-5_7") (pintype "passive"))
      (node (ref "U6") (pin "60") (pinfunction "DP0_60") (pintype "passive"))
      (node (ref "USB1") (pin "A6") (pinfunction "D+_A6") (pintype "passive"))
      (node (ref "USB1") (pin "B6") (pinfunction "D+_B6") (pintype "passive"))
    )
    (net (code "53") (name "/UP_RXN") (class "Default")
      (node (ref "U1") (pin "10") (pinfunction "IO-6_10") (pintype "passive"))
      (node (ref "U6") (pin "12") (pinfunction "RXN_UP_12") (pintype "passive"))
      (node (ref "USB1") (pin "A10") (pinfunction "RX2-_A10") (pintype "passive"))
      (node (ref "USB1") (pin "B10") (pinfunction "RX1-_B10") (pintype "passive"))
    )
    (net (code "54") (name "/UP_RXP") (class "Default")
      (node (ref "U1") (pin "1") (pinfunction "IO-1_1") (pintype "passive"))
      (node (ref "U6") (pin "13") (pinfunction "RXP_UP_13") (pintype "passive"))
      (node (ref "USB1") (pin "A11") (pinfunction "RX2+_A11") (pintype "passive"))
      (node (ref "USB1") (pin "B11") (pinfunction "RX1+_B11") (pintype "passive"))
    )
    (net (code "55") (name "/UP_TXN") (class "Default")
      (node (ref "C8") (pin "2") (pinfunction "2_2") (pintype "passive"))
      (node (ref "C9") (pin "1") (pinfunction "1_1") (pintype "passive"))
      (node (ref "U1") (pin "5") (pinfunction "IO-3_5") (pintype "passive"))
      (node (ref "U6") (pin "9") (pinfunction "TXN_UP_9") (pintype "passive"))
    )
    (net (code "56") (name "/UP_TXP") (class "Default")
      (node (ref "C1") (pin "2") (pinfunction "2_2") (pintype "passive"))
      (node (ref "C10") (pin "1") (pinfunction "1_1") (pintype "passive"))
      (node (ref "U1") (pin "6") (pinfunction "IO-4_6") (pintype "passive"))
      (node (ref "U6") (pin "10") (pinfunction "TXP_UP_10") (pintype "passive"))
    )
    (net (code "57") (name "/VAUX1") (class "Default")
      (node (ref "LB6") (pin "1") (pinfunction "1_1") (pintype "passive"))
      (node (ref "USB2") (pin "A9") (pinfunction "VBUS_1_A9") (pintype "passive"))
      (node (ref "USB2") (pin "B9") (pinfunction "VBUS_2_B9") (pintype "passive"))
    )
    (net (code "58") (name "/VMAIN1") (class "Default")
      (node (ref "LB4") (pin "1") (pinfunction "1_1") (pintype "passive"))
      (node (ref "USB1") (pin "A4") (pinfunction "VBUS_A4") (pintype "passive"))
      (node (ref "USB1") (pin "A9") (pinfunction "VBUS_A9") (pintype "passive"))
      (node (ref "USB1") (pin "B4") (pinfunction "VBUS_B4") (pintype "passive"))
      (node (ref "USB1") (pin "B9") (pinfunction "VBUS_B9") (pintype "passive"))
    )
    (net (code "59") (name "/X1") (class "Default")
      (node (ref "C41") (pin "2") (pinfunction "2_2") (pintype "passive"))
      (node (ref "R8") (pin "1") (pinfunction "1_1") (pintype "passive"))
      (node (ref "U6") (pin "6") (pinfunction "X1_6") (pintype "passive"))
      (node (ref "Y1") (pin "1") (pinfunction "OSC1_1") (pintype "passive"))
    )
    (net (code "60") (name "/X2") (class "Default")
      (node (ref "C42") (pin "2") (pinfunction "2_2") (pintype "passive"))
      (node (ref "R8") (pin "2") (pinfunction "2_2") (pintype "passive"))
      (node (ref "U6") (pin "7") (pinfunction "X2_7") (pintype "passive"))
      (node (ref "Y1") (pin "3") (pinfunction "OSC2_3") (pintype "passive"))
    )
    (net (code "61") (name "GND") (class "Default")
      (node (ref "C11") (pin "1") (pinfunction "1_1") (pintype "passive"))
      (node (ref "C12") (pin "1") (pinfunction "1_1") (pintype "passive"))
      (node (ref "C13") (pin "1") (pinfunction "1_1") (pintype "passive"))
      (node (ref "C14") (pin "1") (pinfunction "1_1") (pintype "passive"))
      (node (ref "C15") (pin "1") (pinfunction "1_1") (pintype "passive"))
      (node (ref "C16") (pin "2") (pinfunction "2_2") (pintype "passive"))
      (node (ref "C17") (pin "1") (pinfunction "1_1") (pintype "passive"))
      (node (ref "C18") (pin "1") (pinfunction "1_1") (pintype "passive"))
      (node (ref "C19") (pin "2") (pinfunction "2_2") (pintype "passive"))
      (node (ref "C2") (pin "2") (pinfunction "2_2") (pintype "passive"))
      (node (ref "C20") (pin "2") (pinfunction "2_2") (pintype "passive"))
      (node (ref "C21") (pin "1") (pinfunction "1_1") (pintype "passive"))
      (node (ref "C22") (pin "1") (pinfunction "1_1") (pintype "passive"))
      (node (ref "C23") (pin "1") (pinfunction "1_1") (pintype "passive"))
      (node (ref "C24") (pin "1") (pinfunction "1_1") (pintype "passive"))
      (node (ref "C25") (pin "1") (pinfunction "1_1") (pintype "passive"))
      (node (ref "C26") (pin "1") (pinfunction "1_1") (pintype "passive"))
      (node (ref "C27") (pin "1") (pinfunction "1_1") (pintype "passive"))
      (node (ref "C28") (pin "1") (pinfunction "1_1") (pintype "passive"))
      (node (ref "C29") (pin "1") (pinfunction "1_1") (pintype "passive"))
      (node (ref "C3") (pin "2") (pinfunction "2_2") (pintype "passive"))
      (node (ref "C30") (pin "1") (pinfunction "1_1") (pintype "passive"))
      (node (ref "C31") (pin "1") (pinfunction "1_1") (pintype "passive"))
      (node (ref "C32") (pin "1") (pinfunction "1_1") (pintype "passive"))
      (node (ref "C33") (pin "1") (pinfunction "1_1") (pintype "passive"))
      (node (ref "C34") (pin "1") (pinfunction "1_1") (pintype "passive"))
      (node (ref "C35") (pin "1") (pinfunction "1_1") (pintype "passive"))
      (node (ref "C36") (pin "1") (pinfunction "1_1") (pintype "passive"))
      (node (ref "C37") (pin "1") (pinfunction "1_1") (pintype "passive"))
      (node (ref "C38") (pin "2") (pinfunction "2_2") (pintype "passive"))
      (node (ref "C39") (pin "1") (pinfunction "1_1") (pintype "passive"))
      (node (ref "C4") (pin "2") (pinfunction "2_2") (pintype "passive"))
      (node (ref "C40") (pin "1") (pinfunction "1_1") (pintype "passive"))
      (node (ref "C41") (pin "1") (pinfunction "1_1") (pintype "passive"))
      (node (ref "C42") (pin "1") (pinfunction "1_1") (pintype "passive"))
      (node (ref "C43") (pin "1") (pinfunction "1_1") (pintype "passive"))
      (node (ref "C44") (pin "2") (pinfunction "2_2") (pintype "passive"))
      (node (ref "C45") (pin "2") (pinfunction "2_2") (pintype "passive"))
      (node (ref "C47") (pin "1") (pinfunction "1_1") (pintype "passive"))
      (node (ref "C48") (pin "1") (pinfunction "1_1") (pintype "passive"))
      (node (ref "C49") (pin "2") (pinfunction "2_2") (pintype "passive"))
      (node (ref "C5") (pin "2") (pinfunction "2_2") (pintype "passive"))
      (node (ref "C50") (pin "1") (pinfunction "1_1") (pintype "passive"))
      (node (ref "C51") (pin "1") (pinfunction "1_1") (pintype "passive"))
      (node (ref "C52") (pin "2") (pinfunction "2_2") (pintype "passive"))
      (node (ref "C53") (pin "1") (pinfunction "1_1") (pintype "passive"))
      (node (ref "C6") (pin "1") (pinfunction "1_1") (pintype "passive"))
      (node (ref "C7") (pin "1") (pinfunction "1_1") (pintype "passive"))
      (node (ref "D10") (pin "1") (pinfunction "A_1") (pintype "passive"))
      (node (ref "D11") (pin "1") (pinfunction "A_1") (pintype "passive"))
      (node (ref "DOWN1") (pin "4") (pinfunction "GND_4") (pintype "power_in"))
      (node (ref "DOWN1") (pin "7") (pinfunction "GND_7") (pintype "power_in"))
      (node (ref "DOWN2") (pin "4") (pinfunction "GND_4") (pintype "power_in"))
      (node (ref "DOWN2") (pin "7") (pinfunction "GND_7") (pintype "power_in"))
      (node (ref "DOWN3") (pin "4") (pinfunction "GND_4") (pintype "power_in"))
      (node (ref "DOWN3") (pin "7") (pinfunction "GND_7") (pintype "power_in"))
      (node (ref "DOWN4") (pin "4") (pinfunction "GND_4") (pintype "power_in"))
      (node (ref "DOWN4") (pin "7") (pinfunction "GND_7") (pintype "power_in"))
      (node (ref "R1") (pin "2") (pinfunction "2_2") (pintype "passive"))
      (node (ref "R10") (pin "1") (pinfunction "1_1") (pintype "passive"))
      (node (ref "R12") (pin "2") (pinfunction "2_2") (pintype "passive"))
      (node (ref "R13") (pin "2") (pinfunction "2_2") (pintype "passive"))
      (node (ref "R14") (pin "2") (pinfunction "2_2") (pintype "passive"))
      (node (ref "R15") (pin "1") (pinfunction "1_1") (pintype "passive"))
      (node (ref "R16") (pin "1") (pinfunction "1_1") (pintype "passive"))
      (node (ref "R17") (pin "1") (pinfunction "1_1") (pintype "passive"))
      (node (ref "R18") (pin "1") (pinfunction "1_1") (pintype "passive"))
      (node (ref "R19") (pin "2") (pinfunction "2_2") (pintype "passive"))
      (node (ref "R3") (pin "2") (pinfunction "2_2") (pintype "passive"))
      (node (ref "R30") (pin "2") (pinfunction "2_2") (pintype "passive"))
      (node (ref "R31") (pin "2") (pinfunction "2_2") (pintype "passive"))
      (node (ref "R32") (pin "2") (pinfunction "2_2") (pintype "passive"))
      (node (ref "R33") (pin "2") (pinfunction "2_2") (pintype "passive"))
      (node (ref "R34") (pin "2") (pinfunction "2_2") (pintype "passive"))
      (node (ref "R35") (pin "2") (pinfunction "2_2") (pintype "passive"))
      (node (ref "R36") (pin "2") (pinfunction "2_2") (pintype "passive"))
      (node (ref "R4") (pin "2") (pinfunction "2_2") (pintype "passive"))
      (node (ref "R5") (pin "2") (pinfunction "2_2") (pintype "passive"))
      (node (ref "R6") (pin "2") (pinfunction "2_2") (pintype "passive"))
      (node (ref "R9") (pin "2") (pinfunction "2_2") (pintype "passive"))
      (node (ref "U1") (pin "11") (pinfunction "PAD_11") (pintype "passive"))
      (node (ref "U1") (pin "9") (pinfunction "GND_9") (pintype "passive"))
      (node (ref "U10") (pin "6") (pinfunction "GND_6") (pintype "passive"))
      (node (ref "U2") (pin "9") (pinfunction "GND_9") (pintype "passive"))
      (node (ref "U3") (pin "9") (pinfunction "GND_9") (pintype "passive"))
      (node (ref "U4") (pin "2") (pinfunction "GND_2") (pintype "passive"))
      (node (ref "U5") (pin "9") (pinfunction "GND_9") (pintype "passive"))
      (node (ref "U6") (pin "11") (pinfunction "GND_11") (pintype "passive"))
      (node (ref "U6") (pin "18") (pinfunction "GND_18") (pintype "passive"))
      (node (ref "U6") (pin "26") (pinfunction "GND_26") (pintype "passive"))
      (node (ref "U6") (pin "33") (pinfunction "GND_33") (pintype "passive"))
      (node (ref "U6") (pin "40") (pinfunction "GND_40") (pintype "passive"))
      (node (ref "U6") (pin "67") (pinfunction "GND_67") (pintype "passive"))
      (node (ref "U6") (pin "G1") (pinfunction "G1_G1") (pintype "passive"))
      (node (ref "U7") (pin "9") (pinfunction "GND_9") (pintype "passive"))
      (node (ref "U8") (pin "4") (pinfunction "VSS_4") (pintype "passive"))
      (node (ref "U9") (pin "6") (pinfunction "GND_6") (pintype "passive"))
      (node (ref "USB1") (pin "A1") (pinfunction "GND_A1") (pintype "passive"))
      (node (ref "USB1") (pin "A12") (pinfunction "GND_A12") (pintype "passive"))
      (node (ref "USB1") (pin "B1") (pinfunction "GND_B1") (pintype "passive"))
      (node (ref "USB1") (pin "B12") (pinfunction "GND_B12") (pintype "passive"))
      (node (ref "USB2") (pin "A12") (pinfunction "GND_1_A12") (pintype "passive"))
      (node (ref "USB2") (pin "B12") (pinfunction "GND_2_B12") (pintype "passive"))
    )
    (net (code "62") (name "Net-(D2-PadK)") (class "Default")
      (node (ref "D2") (pin "K") (pinfunction "K_K") (pintype "passive"))
      (node (ref "D4") (pin "K") (pinfunction "K_K") (pintype "passive"))
      (node (ref "R15") (pin "2") (pinfunction "2_2") (pintype "passive"))
    )
    (net (code "63") (name "Net-(D3-PadK)") (class "Default")
      (node (ref "D3") (pin "K") (pinfunction "K_K") (pintype "passive"))
      (node (ref "D5") (pin "K") (pinfunction "K_K") (pintype "passive"))
      (node (ref "R16") (pin "2") (pinfunction "2_2") (pintype "passive"))
    )
    (net (code "64") (name "Net-(D6-PadK)") (class "Default")
      (node (ref "D6") (pin "K") (pinfunction "K_K") (pintype "passive"))
      (node (ref "D8") (pin "K") (pinfunction "K_K") (pintype "passive"))
      (node (ref "R17") (pin "2") (pinfunction "2_2") (pintype "passive"))
    )
    (net (code "65") (name "Net-(D7-PadK)") (class "Default")
      (node (ref "D7") (pin "K") (pinfunction "K_K") (pintype "passive"))
      (node (ref "D9") (pin "K") (pinfunction "K_K") (pintype "passive"))
      (node (ref "R18") (pin "2") (pinfunction "2_2") (pintype "passive"))
    )
    (net (code "66") (name "Net-(DOWN1-VCC)") (class "Default")
      (node (ref "DOWN1") (pin "1") (pinfunction "VCC_1") (pintype "power_in"))
      (node (ref "LB1") (pin "2") (pinfunction "2_2") (pintype "passive"))
    )
    (net (code "67") (name "Net-(DOWN2-VCC)") (class "Default")
      (node (ref "DOWN2") (pin "1") (pinfunction "VCC_1") (pintype "power_in"))
      (node (ref "LB5") (pin "2") (pinfunction "2_2") (pintype "passive"))
    )
    (net (code "68") (name "Net-(DOWN3-VCC)") (class "Default")
      (node (ref "DOWN3") (pin "1") (pinfunction "VCC_1") (pintype "power_in"))
      (node (ref "LB8") (pin "2") (pinfunction "2_2") (pintype "passive"))
    )
    (net (code "69") (name "Net-(DOWN4-VCC)") (class "Default")
      (node (ref "DOWN4") (pin "1") (pinfunction "VCC_1") (pintype "power_in"))
      (node (ref "LB9") (pin "2") (pinfunction "2_2") (pintype "passive"))
    )
    (net (code "70") (name "Net-(U4-FB)") (class "Default")
      (node (ref "C46") (pin "1") (pinfunction "1_1") (pintype "passive"))
      (node (ref "R11") (pin "2") (pinfunction "2_2") (pintype "passive"))
      (node (ref "R13") (pin "1") (pinfunction "1_1") (pintype "passive"))
      (node (ref "U4") (pin "5") (pinfunction "FB_5") (pintype "passive"))
    )
    (net (code "71") (name "Net-(U4-LX)") (class "Default")
      (node (ref "LB7") (pin "1") (pinfunction "1_1") (pintype "passive"))
      (node (ref "U4") (pin "3") (pinfunction "LX_3") (pintype "passive"))
    )
    (net (code "72") (name "Net-(U8-~{HOLD})") (class "Default")
      (node (ref "R21") (pin "1") (pinfunction "1_1") (pintype "passive"))
      (node (ref "U8") (pin "7") (pinfunction "~{HOLD}_7") (pintype "passive"))
    )
    (net (code "73") (name "Net-(U8-~{WP})") (class "Default")
      (node (ref "R20") (pin "2") (pinfunction "2_2") (pintype "passive"))
      (node (ref "R30") (pin "1") (pinfunction "1_1") (pintype "passive"))
      (node (ref "U8") (pin "3") (pinfunction "~{WP}_3") (pintype "passive"))
    )
    (net (code "74") (name "Net-(USB1-TX1+)") (class "Default")
      (node (ref "C1") (pin "1") (pinfunction "1_1") (pintype "passive"))
      (node (ref "USB1") (pin "A2") (pinfunction "TX1+_A2") (pintype "passive"))
    )
    (net (code "75") (name "Net-(USB1-TX1-)") (class "Default")
      (node (ref "C8") (pin "1") (pinfunction "1_1") (pintype "passive"))
      (node (ref "USB1") (pin "A3") (pinfunction "TX1-_A3") (pintype "passive"))
    )
    (net (code "76") (name "Net-(USB1-TX2+)") (class "Default")
      (node (ref "C10") (pin "2") (pinfunction "2_2") (pintype "passive"))
      (node (ref "USB1") (pin "B2") (pinfunction "TX2+_B2") (pintype "passive"))
    )
    (net (code "77") (name "Net-(USB1-TX2-)") (class "Default")
      (node (ref "C9") (pin "2") (pinfunction "2_2") (pintype "passive"))
      (node (ref "USB1") (pin "B3") (pinfunction "TX2-_B3") (pintype "passive"))
    )
    (net (code "78") (name "SHIEL3") (class "Default")
      (node (ref "C11") (pin "2") (pinfunction "2_2") (pintype "passive"))
      (node (ref "R4") (pin "1") (pinfunction "1_1") (pintype "passive"))
    )
    (net (code "79") (name "SHIELD1") (class "Default")
      (node (ref "C18") (pin "2") (pinfunction "2_2") (pintype "passive"))
      (node (ref "R6") (pin "1") (pinfunction "1_1") (pintype "passive"))
      (node (ref "USB1") (pin "1") (pinfunction "SH1_1") (pintype "passive"))
      (node (ref "USB1") (pin "2") (pinfunction "SH2_2") (pintype "passive"))
      (node (ref "USB1") (pin "3") (pinfunction "SH3_3") (pintype "passive"))
      (node (ref "USB1") (pin "4") (pinfunction "SH4_4") (pintype "passive"))
    )
    (net (code "80") (name "SHIELD2") (class "Default")
      (node (ref "C43") (pin "2") (pinfunction "2_2") (pintype "passive"))
      (node (ref "R12") (pin "1") (pinfunction "1_1") (pintype "passive"))
      (node (ref "USB2") (pin "MH1") (pinfunction "MH1_MH1") (pintype "passive"))
      (node (ref "USB2") (pin "MH2") (pinfunction "MH2_MH2") (pintype "passive"))
      (node (ref "USB2") (pin "MH3") (pinfunction "MH3_MH3") (pintype "passive"))
      (node (ref "USB2") (pin "MH4") (pinfunction "MH4_MH4") (pintype "passive"))
    )
    (net (code "81") (name "SHIELD3") (class "Default")
      (node (ref "DOWN1") (pin "G1") (pinfunction "HAND1_G1") (pintype "passive"))
      (node (ref "DOWN1") (pin "G2") (pinfunction "HAND2_G2") (pintype "passive"))
    )
    (net (code "82") (name "SHIELD4") (class "Default")
      (node (ref "C28") (pin "2") (pinfunction "2_2") (pintype "passive"))
      (node (ref "DOWN2") (pin "G1") (pinfunction "HAND1_G1") (pintype "passive"))
      (node (ref "DOWN2") (pin "G2") (pinfunction "HAND2_G2") (pintype "passive"))
      (node (ref "R9") (pin "1") (pinfunction "1_1") (pintype "passive"))
    )
    (net (code "83") (name "SHIELD5") (class "Default")
      (node (ref "C48") (pin "2") (pinfunction "2_2") (pintype "passive"))
      (node (ref "DOWN3") (pin "G1") (pinfunction "HAND1_G1") (pintype "passive"))
      (node (ref "DOWN3") (pin "G2") (pinfunction "HAND2_G2") (pintype "passive"))
      (node (ref "R14") (pin "1") (pinfunction "1_1") (pintype "passive"))
    )
    (net (code "84") (name "SHIELD6") (class "Default")
      (node (ref "C51") (pin "2") (pinfunction "2_2") (pintype "passive"))
      (node (ref "DOWN4") (pin "G1") (pinfunction "HAND1_G1") (pintype "passive"))
      (node (ref "DOWN4") (pin "G2") (pinfunction "HAND2_G2") (pintype "passive"))
      (node (ref "R19") (pin "1") (pinfunction "1_1") (pintype "passive"))
    )
    (net (code "85") (name "VAUX") (class "Default")
      (node (ref "C2") (pin "1") (pinfunction "1_1") (pintype "passive"))
      (node (ref "C6") (pin "2") (pinfunction "2_2") (pintype "passive"))
      (node (ref "D1") (pin "1") (pinfunction "A_1") (pintype "passive"))
      (node (ref "D10") (pin "2") (pinfunction "K_2") (pintype "passive"))
      (node (ref "LB6") (pin "2") (pinfunction "2_2") (pintype "passive"))
      (node (ref "R1") (pin "1") (pinfunction "1_1") (pintype "passive"))
      (node (ref "R2") (pin "2") (pinfunction "2_2") (pintype "passive"))
    )
    (net (code "86") (name "VCC") (class "Default")
      (node (ref "C19") (pin "1") (pinfunction "1_1") (pintype "passive"))
      (node (ref "C24") (pin "2") (pinfunction "2_2") (pintype "passive"))
      (node (ref "C44") (pin "1") (pinfunction "1_1") (pintype "passive"))
      (node (ref "D1") (pin "2") (pinfunction "K_2") (pintype "passive"))
      (node (ref "Q1") (pin "2") (pinfunction "SOURCE_2") (pintype "passive"))
      (node (ref "R7") (pin "2") (pinfunction "2_2") (pintype "passive"))
      (node (ref "U1") (pin "2") (pinfunction "VCC_2") (pintype "passive"))
      (node (ref "U10") (pin "7") (pinfunction "IN_7") (pintype "passive"))
      (node (ref "U4") (pin "1") (pinfunction "EN_1") (pintype "passive"))
      (node (ref "U4") (pin "4") (pinfunction "VIN_4") (pintype "passive"))
      (node (ref "U6") (pin "86") (pinfunction "V5_LDO_86") (pintype "passive"))
      (node (ref "U9") (pin "7") (pinfunction "IN_7") (pintype "passive"))
    )
    (net (code "87") (name "VD12") (class "Default")
      (node (ref "C12") (pin "2") (pinfunction "2_2") (pintype "passive"))
      (node (ref "C13") (pin "2") (pinfunction "2_2") (pintype "passive"))
      (node (ref "C14") (pin "2") (pinfunction "2_2") (pintype "passive"))
      (node (ref "C15") (pin "2") (pinfunction "2_2") (pintype "passive"))
      (node (ref "C45") (pin "1") (pinfunction "1_1") (pintype "passive"))
      (node (ref "C46") (pin "2") (pinfunction "2_2") (pintype "passive"))
      (node (ref "C47") (pin "2") (pinfunction "2_2") (pintype "passive"))
      (node (ref "LB2") (pin "1") (pinfunction "1_1") (pintype "passive"))
      (node (ref "LB7") (pin "2") (pinfunction "2_2") (pintype "passive"))
      (node (ref "R11") (pin "1") (pinfunction "1_1") (pintype "passive"))
      (node (ref "U6") (pin "44") (pinfunction "DVDD12_44") (pintype "passive"))
      (node (ref "U6") (pin "49") (pinfunction "DVDD12_49") (pintype "passive"))
      (node (ref "U6") (pin "57") (pinfunction "DVDD12_57") (pintype "passive"))
      (node (ref "U6") (pin "75") (pinfunction "DVDD12_75") (pintype "passive"))
    )
    (net (code "88") (name "VD33") (class "Default")
      (node (ref "C20") (pin "1") (pinfunction "1_1") (pintype "passive"))
      (node (ref "C25") (pin "2") (pinfunction "2_2") (pintype "passive"))
      (node (ref "C26") (pin "2") (pinfunction "2_2") (pintype "passive"))
      (node (ref "C27") (pin "2") (pinfunction "2_2") (pintype "passive"))
      (node (ref "C4") (pin "1") (pinfunction "1_1") (pintype "passive"))
      (node (ref "LB3") (pin "1") (pinfunction "1_1") (pintype "passive"))
      (node (ref "R20") (pin "1") (pinfunction "1_1") (pintype "passive"))
      (node (ref "R21") (pin "2") (pinfunction "2_2") (pintype "passive"))
      (node (ref "R22") (pin "1") (pinfunction "1_1") (pintype "passive"))
      (node (ref "R23") (pin "1") (pinfunction "1_1") (pintype "passive"))
      (node (ref "R24") (pin "1") (pinfunction "1_1") (pintype "passive"))
      (node (ref "R25") (pin "1") (pinfunction "1_1") (pintype "passive"))
      (node (ref "R26") (pin "1") (pinfunction "1_1") (pintype "passive"))
      (node (ref "R27") (pin "1") (pinfunction "1_1") (pintype "passive"))
      (node (ref "R28") (pin "1") (pinfunction "1_1") (pintype "passive"))
      (node (ref "R29") (pin "1") (pinfunction "1_1") (pintype "passive"))
      (node (ref "U6") (pin "58") (pinfunction "DVDD_58") (pintype "passive"))
      (node (ref "U6") (pin "73") (pinfunction "DVDD_73") (pintype "passive"))
      (node (ref "U6") (pin "85") (pinfunction "V33_OUT_85") (pintype "passive"))
      (node (ref "U8") (pin "8") (pinfunction "VCC_8") (pintype "passive"))
    )
    (net (code "89") (name "VDP1") (class "Default")
      (node (ref "C16") (pin "1") (pinfunction "1_1") (pintype "passive"))
      (node (ref "C17") (pin "2") (pinfunction "2_2") (pintype "passive"))
      (node (ref "LB1") (pin "1") (pinfunction "1_1") (pintype "passive"))
      (node (ref "U2") (pin "2") (pinfunction "VCC_2") (pintype "passive"))
      (node (ref "U9") (pin "8") (pinfunction "OUTA_8") (pintype "passive"))
    )
    (net (code "90") (name "VDP2") (class "Default")
      (node (ref "C38") (pin "1") (pinfunction "1_1") (pintype "passive"))
      (node (ref "C39") (pin "2") (pinfunction "2_2") (pintype "passive"))
      (node (ref "LB5") (pin "1") (pinfunction "1_1") (pintype "passive"))
      (node (ref "U3") (pin "2") (pinfunction "VCC_2") (pintype "passive"))
      (node (ref "U9") (pin "5") (pinfunction "OUTB_5") (pintype "passive"))
    )
    (net (code "91") (name "VDP3") (class "Default")
      (node (ref "C49") (pin "1") (pinfunction "1_1") (pintype "passive"))
      (node (ref "C50") (pin "2") (pinfunction "2_2") (pintype "passive"))
      (node (ref "LB8") (pin "1") (pinfunction "1_1") (pintype "passive"))
      (node (ref "U10") (pin "5") (pinfunction "OUTB_5") (pintype "passive"))
      (node (ref "U10") (pin "8") (pinfunction "OUTA_8") (pintype "passive"))
      (node (ref "U5") (pin "2") (pinfunction "VCC_2") (pintype "passive"))
    )
    (net (code "92") (name "VDP4") (class "Default")
      (node (ref "C52") (pin "1") (pinfunction "1_1") (pintype "passive"))
      (node (ref "C53") (pin "2") (pinfunction "2_2") (pintype "passive"))
      (node (ref "LB9") (pin "1") (pinfunction "1_1") (pintype "passive"))
      (node (ref "U7") (pin "2") (pinfunction "VCC_2") (pintype "passive"))
    )
    (net (code "93") (name "VMAIN") (class "Default")
      (node (ref "C3") (pin "1") (pinfunction "1_1") (pintype "passive"))
      (node (ref "C7") (pin "2") (pinfunction "2_2") (pintype "passive"))
      (node (ref "D11") (pin "2") (pinfunction "K_2") (pintype "passive"))
      (node (ref "LB4") (pin "2") (pinfunction "2_2") (pintype "passive"))
      (node (ref "Q1") (pin "3") (pinfunction "DRAIN_3") (pintype "passive"))
      (node (ref "U6") (pin "55") (pinfunction "VBUS_55") (pintype "passive"))
    )
    (net (code "94") (name "VP12") (class "Default")
      (node (ref "C29") (pin "2") (pinfunction "2_2") (pintype "passive"))
      (node (ref "C30") (pin "2") (pinfunction "2_2") (pintype "passive"))
      (node (ref "C31") (pin "2") (pinfunction "2_2") (pintype "passive"))
      (node (ref "C32") (pin "2") (pinfunction "2_2") (pintype "passive"))
      (node (ref "C33") (pin "2") (pinfunction "2_2") (pintype "passive"))
      (node (ref "C34") (pin "2") (pinfunction "2_2") (pintype "passive"))
      (node (ref "C35") (pin "2") (pinfunction "2_2") (pintype "passive"))
      (node (ref "C36") (pin "2") (pinfunction "2_2") (pintype "passive"))
      (node (ref "C37") (pin "2") (pinfunction "2_2") (pintype "passive"))
      (node (ref "LB2") (pin "2") (pinfunction "2_2") (pintype "passive"))
      (node (ref "U6") (pin "14") (pinfunction "VP12_14") (pintype "passive"))
      (node (ref "U6") (pin "15") (pinfunction "VP12_15") (pintype "passive"))
      (node (ref "U6") (pin "21") (pinfunction "VP12_21") (pintype "passive"))
      (node (ref "U6") (pin "23") (pinfunction "VP12_23") (pintype "passive"))
      (node (ref "U6") (pin "29") (pinfunction "VP12_29") (pintype "passive"))
      (node (ref "U6") (pin "30") (pinfunction "VP12_30") (pintype "passive"))
      (node (ref "U6") (pin "36") (pinfunction "VP12_36") (pintype "passive"))
      (node (ref "U6") (pin "37") (pinfunction "VP12_37") (pintype "passive"))
      (node (ref "U6") (pin "43") (pinfunction "VP12_43") (pintype "passive"))
    )
    (net (code "95") (name "VP33") (class "Default")
      (node (ref "C21") (pin "2") (pinfunction "2_2") (pintype "passive"))
      (node (ref "C22") (pin "2") (pinfunction "2_2") (pintype "passive"))
      (node (ref "C23") (pin "2") (pinfunction "2_2") (pintype "passive"))
      (node (ref "C5") (pin "1") (pinfunction "1_1") (pintype "passive"))
      (node (ref "LB3") (pin "2") (pinfunction "2_2") (pintype "passive"))
      (node (ref "U6") (pin "63") (pinfunction "AVDD_63") (pintype "passive"))
      (node (ref "U6") (pin "66") (pinfunction "AVDD_66") (pintype "passive"))
      (node (ref "U6") (pin "70") (pinfunction "AVDD_70") (pintype "passive"))
    )
    (net (code "96") (name "unconnected-(R2-Pad1)") (class "Default")
      (node (ref "R2") (pin "1") (pinfunction "1_1") (pintype "passive"))
    )
    (net (code "97") (name "unconnected-(U1-NC-Pad3)") (class "Default")
      (node (ref "U1") (pin "3") (pinfunction "NC_3") (pintype "passive+no_connect"))
    )
    (net (code "98") (name "unconnected-(U1-NC-Pad8)") (class "Default")
      (node (ref "U1") (pin "8") (pinfunction "NC_8") (pintype "passive+no_connect"))
    )
    (net (code "99") (name "unconnected-(U2-NC-Pad3)") (class "Default")
      (node (ref "U2") (pin "3") (pinfunction "NC_3") (pintype "passive+no_connect"))
    )
    (net (code "100") (name "unconnected-(U2-NC-Pad8)") (class "Default")
      (node (ref "U2") (pin "8") (pinfunction "NC_8") (pintype "passive+no_connect"))
    )
    (net (code "101") (name "unconnected-(U2-PAD-Pad11)") (class "Default")
      (node (ref "U2") (pin "11") (pinfunction "PAD_11") (pintype "passive"))
    )
    (net (code "102") (name "unconnected-(U3-NC-Pad3)") (class "Default")
      (node (ref "U3") (pin "3") (pinfunction "NC_3") (pintype "passive+no_connect"))
    )
    (net (code "103") (name "unconnected-(U3-NC-Pad8)") (class "Default")
      (node (ref "U3") (pin "8") (pinfunction "NC_8") (pintype "passive+no_connect"))
    )
    (net (code "104") (name "unconnected-(U3-PAD-Pad11)") (class "Default")
      (node (ref "U3") (pin "11") (pinfunction "PAD_11") (pintype "passive"))
    )
    (net (code "105") (name "unconnected-(U5-NC-Pad3)") (class "Default")
      (node (ref "U5") (pin "3") (pinfunction "NC_3") (pintype "passive+no_connect"))
    )
    (net (code "106") (name "unconnected-(U5-NC-Pad8)") (class "Default")
      (node (ref "U5") (pin "8") (pinfunction "NC_8") (pintype "passive+no_connect"))
    )
    (net (code "107") (name "unconnected-(U5-PAD-Pad11)") (class "Default")
      (node (ref "U5") (pin "11") (pinfunction "PAD_11") (pintype "passive"))
    )
    (net (code "108") (name "unconnected-(U6-NC-Pad4)") (class "Default")
      (node (ref "U6") (pin "4") (pinfunction "NC_4") (pintype "passive"))
    )
    (net (code "109") (name "unconnected-(U6-NC-Pad5)") (class "Default")
      (node (ref "U6") (pin "5") (pinfunction "NC_5") (pintype "passive"))
    )
    (net (code "110") (name "unconnected-(U6-NC-Pad8)") (class "Default")
      (node (ref "U6") (pin "8") (pinfunction "NC_8") (pintype "passive"))
    )
    (net (code "111") (name "unconnected-(U6-NC-Pad22)") (class "Default")
      (node (ref "U6") (pin "22") (pinfunction "NC_22") (pintype "passive"))
    )
    (net (code "112") (name "unconnected-(U6-TEST-Pad76)") (class "Default")
      (node (ref "U6") (pin "76") (pinfunction "TEST_76") (pintype "passive+no_connect"))
    )
    (net (code "113") (name "unconnected-(U7-NC-Pad3)") (class "Default")
      (node (ref "U7") (pin "3") (pinfunction "NC_3") (pintype "passive+no_connect"))
    )
    (net (code "114") (name "unconnected-(U7-NC-Pad8)") (class "Default")
      (node (ref "U7") (pin "8") (pinfunction "NC_8") (pintype "passive+no_connect"))
    )
    (net (code "115") (name "unconnected-(U7-PAD-Pad11)") (class "Default")
      (node (ref "U7") (pin "11") (pinfunction "PAD_11") (pintype "passive"))
    )
    (net (code "116") (name "unconnected-(USB1-SBU1-PadA8)") (class "Default")
      (node (ref "USB1") (pin "A8") (pinfunction "SBU1_A8") (pintype "passive+no_connect"))
    )
    (net (code "117") (name "unconnected-(USB1-SBU2-PadB8)") (class "Default")
      (node (ref "USB1") (pin "B8") (pinfunction "SBU2_B8") (pintype "passive+no_connect"))
    )
    (net (code "118") (name "unconnected-(USB2-CC1-PadA5)") (class "Default")
      (node (ref "USB2") (pin "A5") (pinfunction "CC1_A5") (pintype "passive+no_connect"))
    )
    (net (code "119") (name "unconnected-(USB2-CC2-PadB5)") (class "Default")
      (node (ref "USB2") (pin "B5") (pinfunction "CC2_B5") (pintype "passive+no_connect"))
    )
  )
)
